# recall_mcu_v0_2.net
KiCad netlist of a schematic drawn in Altium Designer
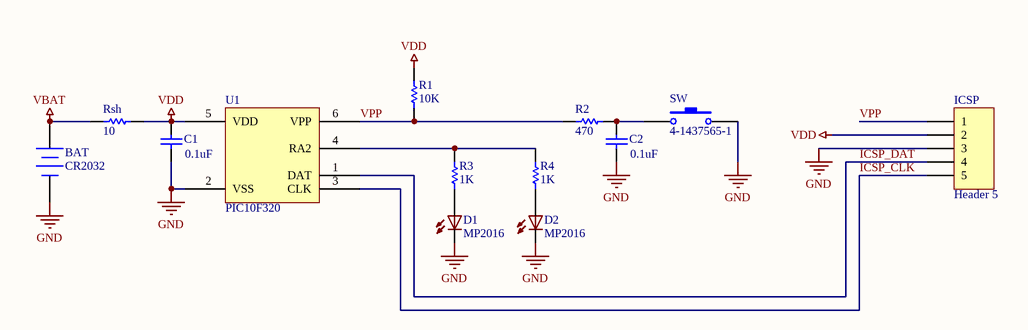
[diagram p0: recall_mcu_v0_2.SchDoc]

(export (version "E")
  (design (tool "Eeschema 10.0.6"))
  (components
    (comp (ref "BAT")
      (value "CR2032")
      (footprint "BAT-HLD-001-THM")
      (fields (field (name "PUBLISHER") "Altium Limited"))
      (libsource (lib "recall") (part "Battery"))
    )
    (comp (ref "C1")
      (value "0.1uF")
      (footprint "CAP_0402R")
      (description "Capacitor")
      (fields (field (name "Comment") "CAP") (field (name "PUBLISHER") "Altium Limited"))
      (libsource (lib "recall") (part "CAP"))
    )
    (comp (ref "C2")
      (value "0.1uF")
      (footprint "CAP_0402R")
      (description "Capacitor")
      (fields (field (name "Comment") "CAP") (field (name "PUBLISHER") "Altium Limited"))
      (libsource (lib "recall") (part "CAP"))
    )
    (comp (ref "D1")
      (value "MP2016")
      (footprint "MP2016_centered")
      (description "MP2016 White LED")
      (libsource (lib "recall") (part "MP2016"))
    )
    (comp (ref "D2")
      (value "MP2016")
      (footprint "MP2016_centered")
      (description "MP2016 White LED")
      (libsource (lib "recall") (part "MP2016"))
    )
    (comp (ref "ICSP")
      (value "Header 5")
      (footprint "HDR1X5_ICSP")
      (description "Header, 5-Pin")
      (fields (field (name "PUBLISHER") "Altium Limited"))
      (libsource (lib "recall") (part "Header 5"))
    )
    (comp (ref "R1")
      (value "10K")
      (footprint "RES_0402")
      (description "Resistor")
      (fields (field (name "Comment") "RES") (field (name "PUBLISHER") "Altium Limited"))
      (libsource (lib "recall") (part "RES"))
    )
    (comp (ref "R2")
      (value "470")
      (footprint "RES_0402")
      (description "Resistor")
      (fields (field (name "Comment") "RES") (field (name "PUBLISHER") "Altium Limited"))
      (libsource (lib "recall") (part "RES"))
    )
    (comp (ref "R3")
      (value "1K")
      (footprint "RES_0402")
      (description "Resistor")
      (fields (field (name "Comment") "RES") (field (name "PUBLISHER") "Altium Limited"))
      (libsource (lib "recall") (part "RES"))
    )
    (comp (ref "R4")
      (value "1K")
      (footprint "RES_0402")
      (description "Resistor")
      (fields (field (name "Comment") "RES") (field (name "PUBLISHER") "Altium Limited"))
      (libsource (lib "recall") (part "RES"))
    )
    (comp (ref "Rsh")
      (value "10")
      (footprint "RES_0402")
      (description "Resistor")
      (fields (field (name "Comment") "RES") (field (name "PUBLISHER") "Altium Limited"))
      (libsource (lib "recall") (part "RES"))
    )
    (comp (ref "SW")
      (value "4-1437565-1")
      (footprint "4-1437565-1")
      (description "Translucent Conductive Silicone Elastomer Switch")
      (fields (field (name "PUBLISHER") "Altium Limited"))
      (libsource (lib "recall") (part "SW-TACT"))
    )
    (comp (ref "U1")
      (value "PIC10F320")
      (footprint "SOT-23-6")
      (description "6-Pin Flash-Based, 8-Bit Microcontroller")
      (libsource (lib "recall") (part "PIC10F320"))
    )
  )
  (nets
    (net (code "1") (name "/ICSP_CLK") (class "Default")
      (node (ref "ICSP") (pin "5") (pinfunction "5_5") (pintype "passive"))
      (node (ref "U1") (pin "3") (pinfunction "CLK_3") (pintype "passive"))
    )
    (net (code "2") (name "/ICSP_DAT") (class "Default")
      (node (ref "ICSP") (pin "4") (pinfunction "4_4") (pintype "passive"))
      (node (ref "U1") (pin "1") (pinfunction "DAT_1") (pintype "passive"))
    )
    (net (code "3") (name "/VPP") (class "Default")
      (node (ref "ICSP") (pin "1") (pinfunction "1_1") (pintype "passive"))
      (node (ref "R1") (pin "1") (pinfunction "1_1") (pintype "passive"))
      (node (ref "R2") (pin "2") (pinfunction "2_2") (pintype "passive"))
      (node (ref "U1") (pin "6") (pinfunction "VPP_6") (pintype "passive"))
    )
    (net (code "4") (name "GND") (class "Default")
      (node (ref "BAT") (pin "2") (pinfunction "-_2") (pintype "passive"))
      (node (ref "C1") (pin "1") (pinfunction "1_1") (pintype "passive"))
      (node (ref "C2") (pin "1") (pinfunction "1_1") (pintype "passive"))
      (node (ref "D1") (pin "C") (pinfunction "C_C") (pintype "passive"))
      (node (ref "D2") (pin "C") (pinfunction "C_C") (pintype "passive"))
      (node (ref "ICSP") (pin "3") (pinfunction "3_3") (pintype "passive"))
      (node (ref "SW") (pin "2") (pinfunction "2_2") (pintype "passive"))
      (node (ref "U1") (pin "2") (pinfunction "VSS_2") (pintype "passive"))
    )
    (net (code "5") (name "Net-(C2-Pad2)") (class "Default")
      (node (ref "C2") (pin "2") (pinfunction "2_2") (pintype "passive"))
      (node (ref "R2") (pin "1") (pinfunction "1_1") (pintype "passive"))
      (node (ref "SW") (pin "1") (pinfunction "1_1") (pintype "passive"))
    )
    (net (code "6") (name "Net-(D1-PadA)") (class "Default")
      (node (ref "D1") (pin "A") (pinfunction "A_A") (pintype "passive"))
      (node (ref "R3") (pin "2") (pinfunction "2_2") (pintype "passive"))
    )
    (net (code "7") (name "Net-(D2-PadA)") (class "Default")
      (node (ref "D2") (pin "A") (pinfunction "A_A") (pintype "passive"))
      (node (ref "R4") (pin "2") (pinfunction "2_2") (pintype "passive"))
    )
    (net (code "8") (name "Net-(U1-RA2)") (class "Default")
      (node (ref "R3") (pin "1") (pinfunction "1_1") (pintype "passive"))
      (node (ref "R4") (pin "1") (pinfunction "1_1") (pintype "passive"))
      (node (ref "U1") (pin "4") (pinfunction "RA2_4") (pintype "passive"))
    )
    (net (code "9") (name "VBAT") (class "Default")
      (node (ref "BAT") (pin "1") (pinfunction "+_1") (pintype "passive"))
      (node (ref "Rsh") (pin "1") (pinfunction "1_1") (pintype "passive"))
    )
    (net (code "10") (name "VDD") (class "Default")
      (node (ref "C1") (pin "2") (pinfunction "2_2") (pintype "passive"))
      (node (ref "ICSP") (pin "2") (pinfunction "2_2") (pintype "passive"))
      (node (ref "R1") (pin "2") (pinfunction "2_2") (pintype "passive"))
      (node (ref "Rsh") (pin "2") (pinfunction "2_2") (pintype "passive"))
      (node (ref "U1") (pin "5") (pinfunction "VDD_5") (pintype "passive"))
    )
  )
)
